# Sheet1.net
KiCad netlist of a schematic drawn in Altium Designer
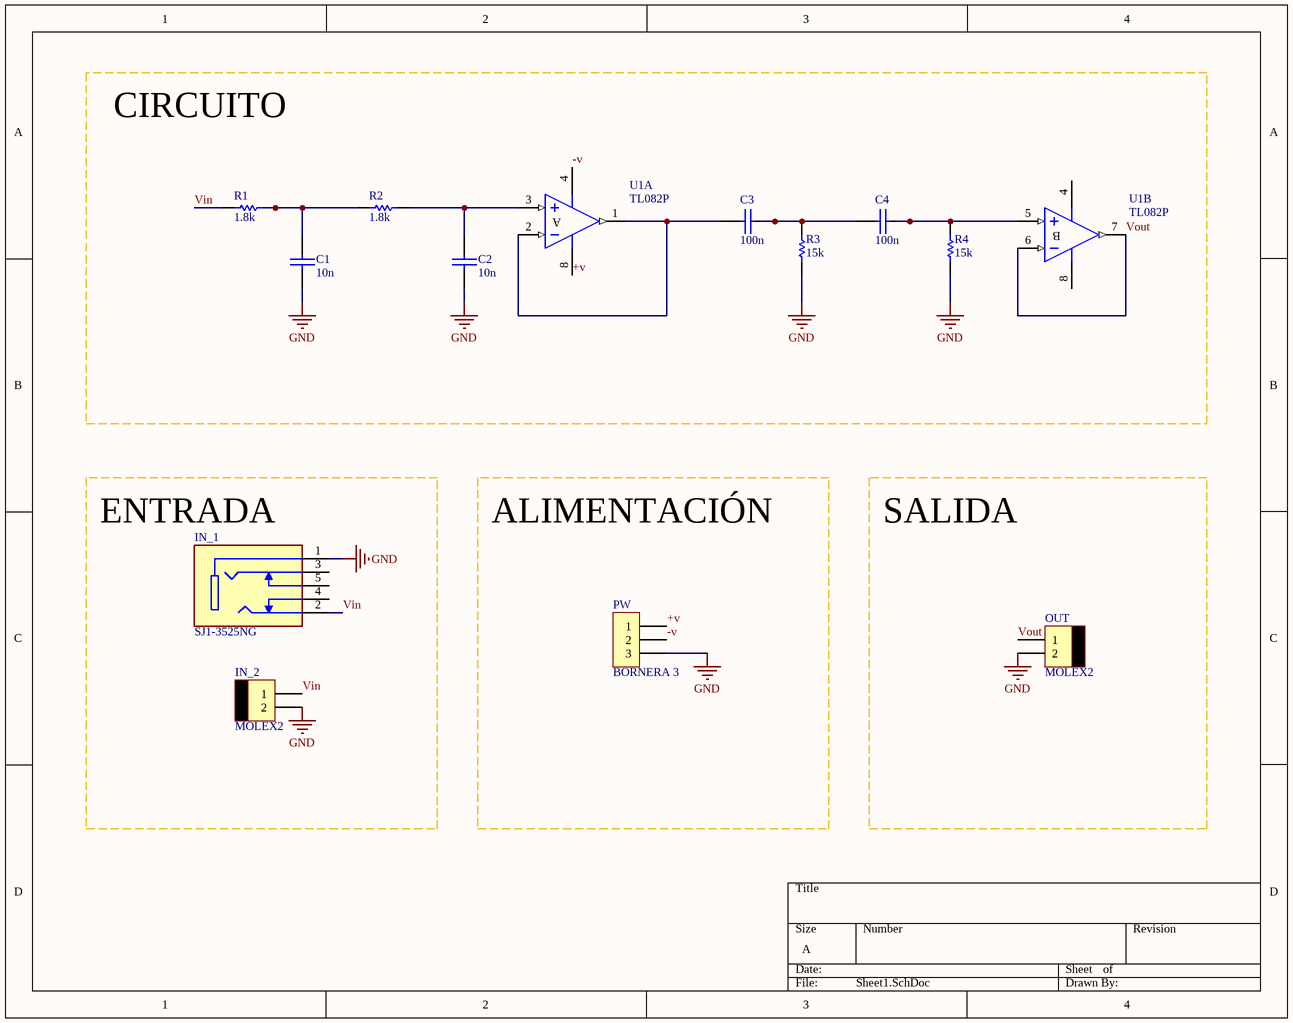
[diagram p0: Sheet1.SchDoc]

(export (version "E")
  (design (tool "Eeschema 10.0.6"))
  (components
    (comp (ref "C1") (value "10n") (footprint "CAP200") (libsource (lib "LIB PIO IX") (part "CAP")))
    (comp (ref "C2") (value "10n") (footprint "CAP200") (libsource (lib "LIB PIO IX") (part "CAP")))
    (comp (ref "C3") (value "100n") (footprint "CAP200") (libsource (lib "LIB PIO IX") (part "CAP")))
    (comp (ref "C4") (value "100n") (footprint "CAP200") (libsource (lib "LIB PIO IX") (part "CAP")))
    (comp (ref "IN_1")
      (value "SJ1-3525NG")
      (footprint "CUI_SJ1-3525NG")
      (fields (field (name "MF") "Same Sky"))
      (libsource (lib "SJ1-3525NG") (part "SJ1-3525NG"))
    )
    (comp (ref "IN_2") (value "MOLEX2") (footprint "MOLEX2") (libsource (lib "LIB PIO IX") (part "MOLEX2")))
    (comp (ref "OUT") (value "MOLEX2") (footprint "MOLEX2") (libsource (lib "") (part "MOLEX2_1")))
    (comp (ref "PW")
      (value "BORNERA 3")
      (footprint "BORNERA3")
      (libsource (lib "LIB PIO IX") (part "BORNERA 3"))
    )
    (comp (ref "R1") (value "1.8k") (footprint "RES400") (libsource (lib "LIB PIO IX") (part "RES")))
    (comp (ref "R2") (value "1.8k") (footprint "RES400") (libsource (lib "LIB PIO IX") (part "RES")))
    (comp (ref "R3") (value "15k") (footprint "RES400") (libsource (lib "LIB PIO IX") (part "RES")))
    (comp (ref "R4") (value "15k") (footprint "RES400") (libsource (lib "LIB PIO IX") (part "RES")))
    (comp (ref "U1")
      (value "TL082P")
      (footprint "P008")
      (description "JFET-Input Operational Amplifier")
      (fields (field (name "PUBLISHER") "Altium Limited"))
      (libsource (lib "TI Operational Amplifier") (part "TL082P"))
    )
  )
  (nets
    (net (code "1") (name "/+v") (class "Default")
      (node (ref "PW") (pin "1") (pinfunction "1_1") (pintype "passive"))
      (node (ref "U1") (pin "8") (pinfunction "V+_8") (pintype "power_in"))
    )
    (net (code "2") (name "/-v") (class "Default")
      (node (ref "PW") (pin "2") (pinfunction "2_2") (pintype "passive"))
      (node (ref "U1") (pin "4") (pinfunction "V-_4") (pintype "power_in"))
    )
    (net (code "3") (name "/Vin") (class "Default")
      (node (ref "IN_1") (pin "2") (pinfunction "2_2") (pintype "passive"))
      (node (ref "IN_2") (pin "1") (pinfunction "1_1") (pintype "passive"))
      (node (ref "R1") (pin "1") (pinfunction "1_1") (pintype "passive"))
    )
    (net (code "4") (name "/Vout") (class "Default")
      (node (ref "OUT") (pin "1") (pinfunction "1_1") (pintype "passive"))
      (node (ref "U1") (pin "6") (pinfunction "IN-_6") (pintype "input"))
      (node (ref "U1") (pin "7") (pinfunction "OUT_7") (pintype "output"))
    )
    (net (code "5") (name "GND") (class "Default")
      (node (ref "C1") (pin "2") (pinfunction "2_2") (pintype "passive"))
      (node (ref "C2") (pin "2") (pinfunction "2_2") (pintype "passive"))
      (node (ref "IN_1") (pin "1") (pinfunction "1_1") (pintype "passive"))
      (node (ref "IN_2") (pin "2") (pinfunction "2_2") (pintype "passive"))
      (node (ref "OUT") (pin "2") (pinfunction "2_2") (pintype "passive"))
      (node (ref "PW") (pin "3") (pinfunction "3_3") (pintype "passive"))
      (node (ref "R3") (pin "1") (pinfunction "1_1") (pintype "passive"))
      (node (ref "R4") (pin "1") (pinfunction "1_1") (pintype "passive"))
    )
    (net (code "6") (name "Net-(C1-Pad1)") (class "Default")
      (node (ref "C1") (pin "1") (pinfunction "1_1") (pintype "passive"))
      (node (ref "R1") (pin "2") (pinfunction "2_2") (pintype "passive"))
      (node (ref "R2") (pin "1") (pinfunction "1_1") (pintype "passive"))
    )
    (net (code "7") (name "Net-(C3-Pad2)") (class "Default")
      (node (ref "C3") (pin "2") (pinfunction "2_2") (pintype "passive"))
      (node (ref "C4") (pin "1") (pinfunction "1_1") (pintype "passive"))
      (node (ref "R3") (pin "2") (pinfunction "2_2") (pintype "passive"))
    )
    (net (code "8") (name "Net-(U1A-IN+)") (class "Default")
      (node (ref "C2") (pin "1") (pinfunction "1_1") (pintype "passive"))
      (node (ref "R2") (pin "2") (pinfunction "2_2") (pintype "passive"))
      (node (ref "U1") (pin "3") (pinfunction "IN+_3") (pintype "input"))
    )
    (net (code "9") (name "Net-(U1A-IN-)") (class "Default")
      (node (ref "C3") (pin "1") (pinfunction "1_1") (pintype "passive"))
      (node (ref "U1") (pin "1") (pinfunction "OUT_1") (pintype "output"))
      (node (ref "U1") (pin "2") (pinfunction "IN-_2") (pintype "input"))
    )
    (net (code "10") (name "Net-(U1B-IN+)") (class "Default")
      (node (ref "C4") (pin "2") (pinfunction "2_2") (pintype "passive"))
      (node (ref "R4") (pin "2") (pinfunction "2_2") (pintype "passive"))
      (node (ref "U1") (pin "5") (pinfunction "IN+_5") (pintype "input"))
    )
    (net (code "11") (name "unconnected-(IN_1-Pad3)") (class "Default")
      (node (ref "IN_1") (pin "3") (pinfunction "3_3") (pintype "passive"))
    )
    (net (code "12") (name "unconnected-(IN_1-Pad4)") (class "Default")
      (node (ref "IN_1") (pin "4") (pinfunction "4_4") (pintype "passive"))
    )
    (net (code "13") (name "unconnected-(IN_1-Pad5)") (class "Default")
      (node (ref "IN_1") (pin "5") (pinfunction "5_5") (pintype "passive"))
    )
    (net (code "14") (name "unconnected-(U1B-V+-Pad8)") (class "Default")
      (node (ref "U1") (pin "8") (pinfunction "V+_8") (pintype "power_in"))
    )
    (net (code "15") (name "unconnected-(U1B-V--Pad4)") (class "Default")
      (node (ref "U1") (pin "4") (pinfunction "V-_4") (pintype "power_in"))
    )
  )
)
